# mcu_stm32f427.net
KiCad netlist of a schematic drawn in Altium Designer
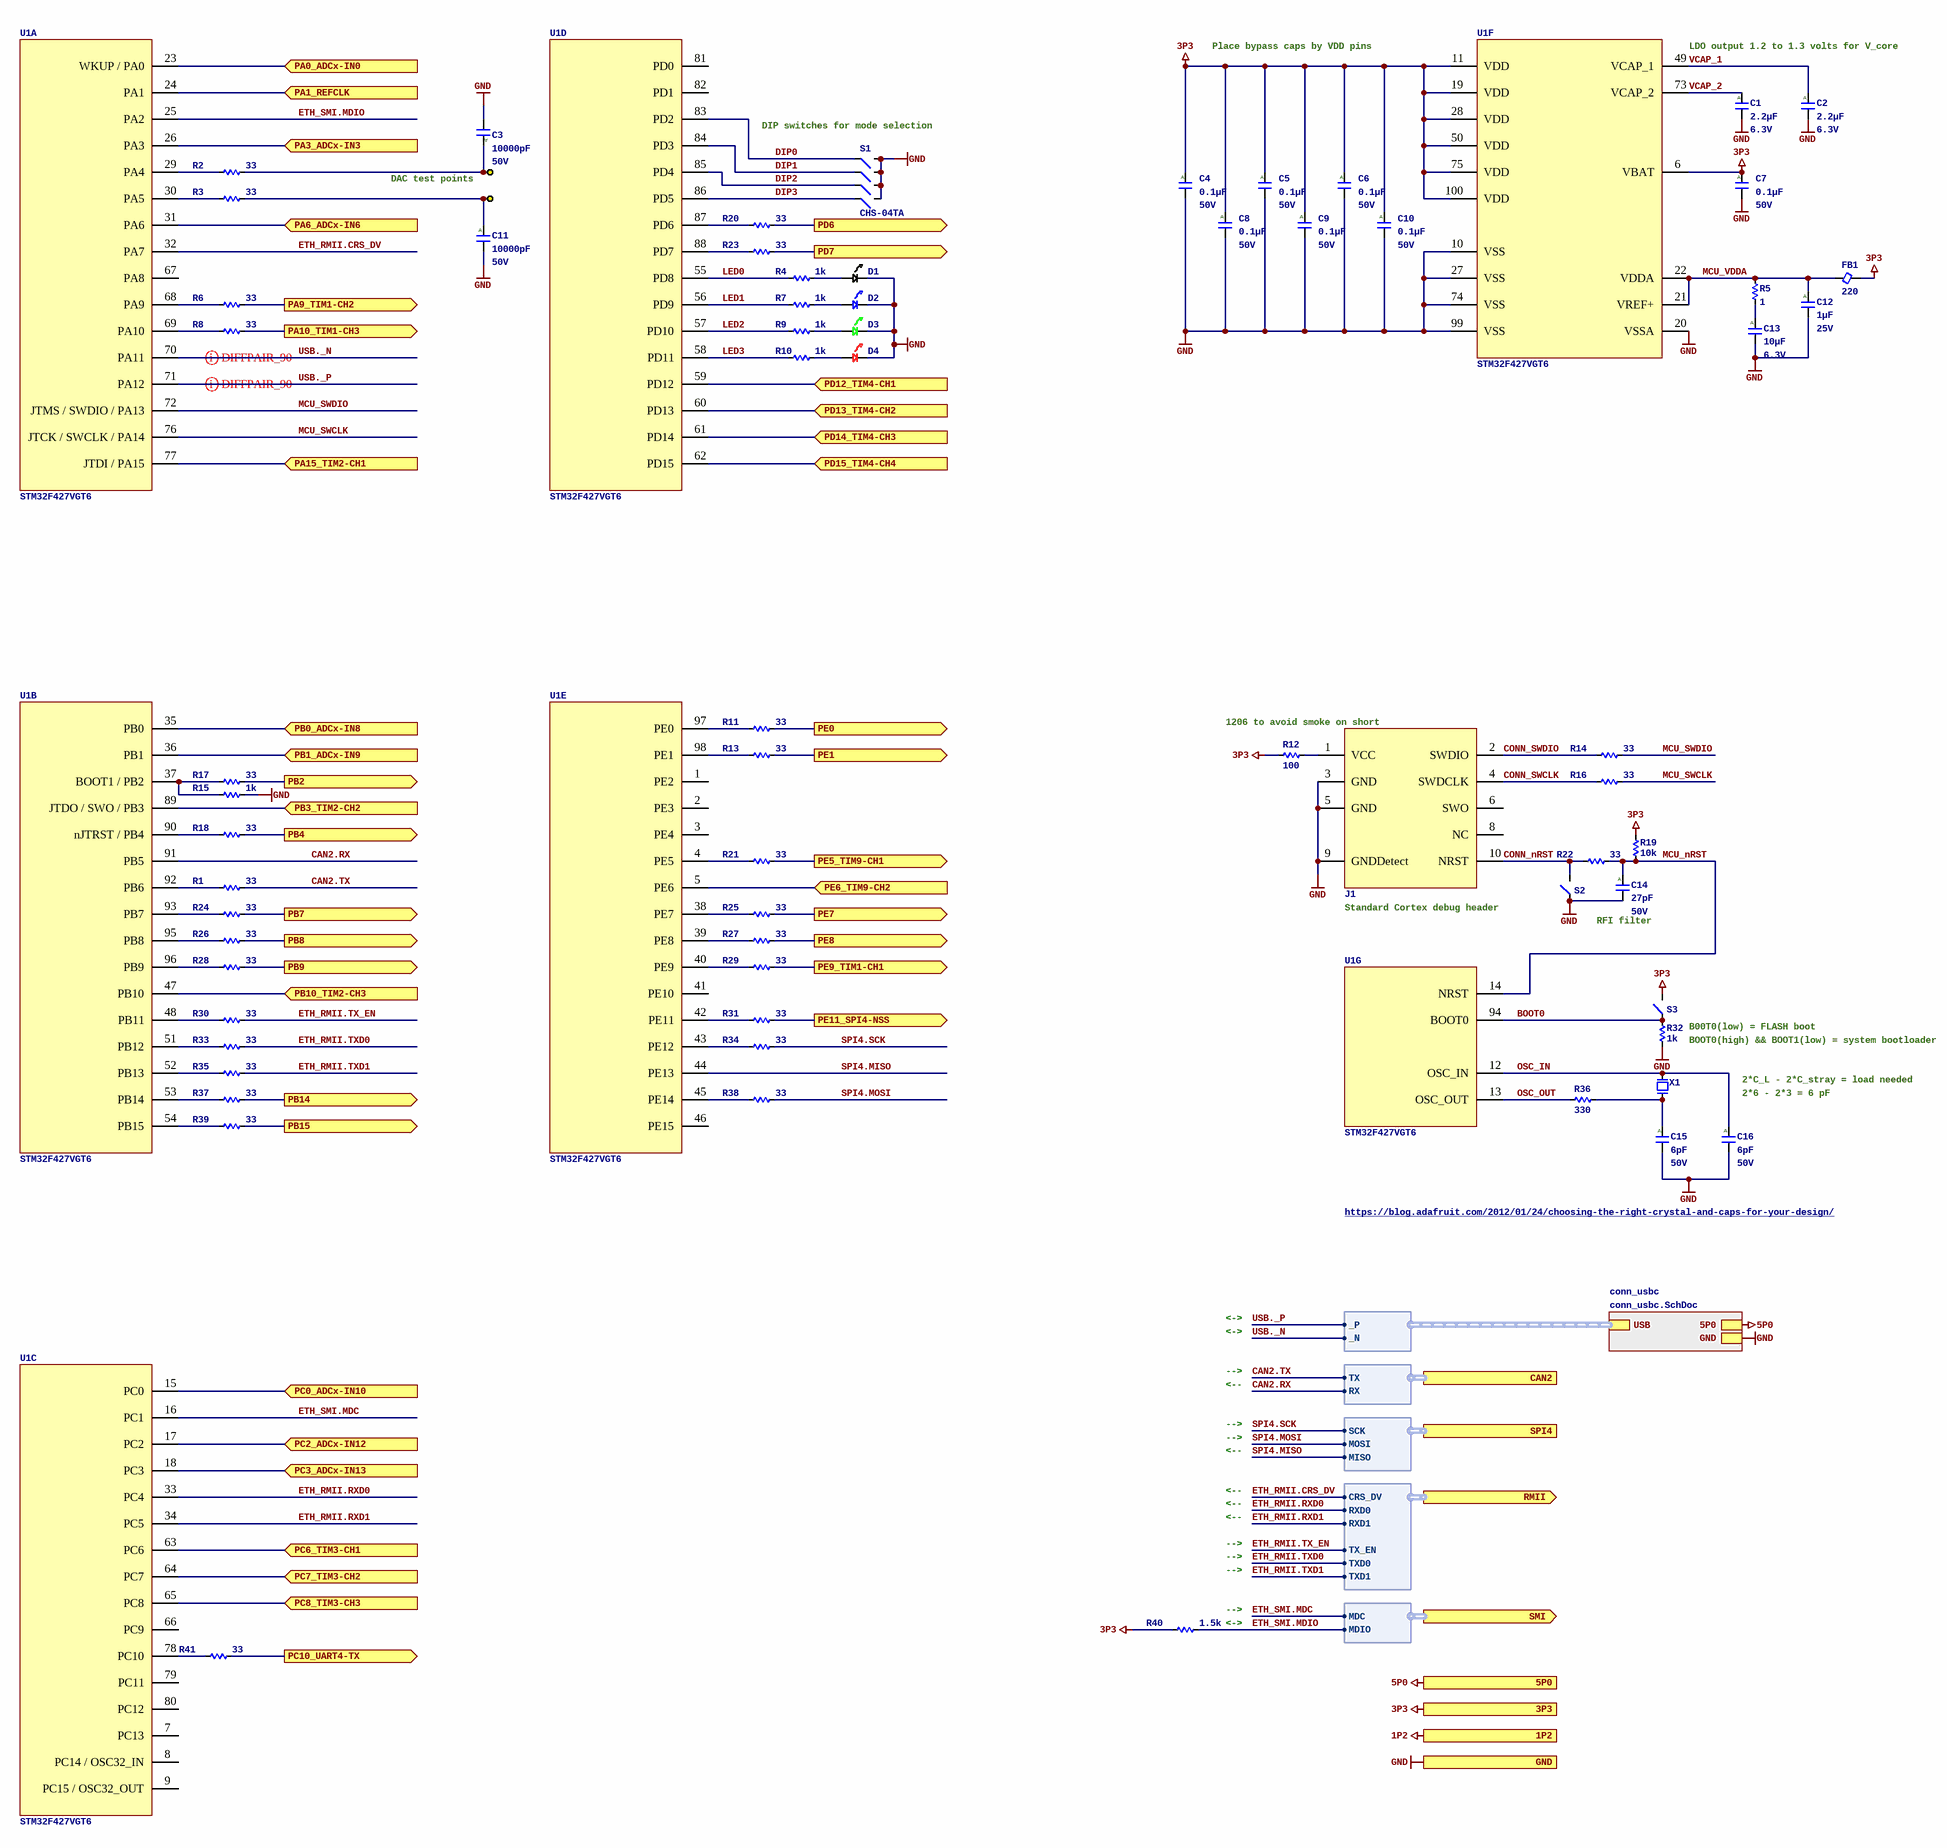
[diagram p0: mcu_stm32f427.SchDoc]

(export (version "E")
  (design (tool "Eeschema 10.0.6"))
  (components
    (comp (ref "C1")
      (value "CGA3E1X7R0J225M080AC")
      (footprint "C0603_0.90MM")
      (description "CAP CER 2.2UF 6.3V X7R 0603")
      (fields
        (field (name "CAPACITANCE") "2.2µF")
        (field (name "VOLTAGE - RATED") "6.3V")
        (field (name "TOLERANCE") "±20%")
        (field (name "MANUFACTURER") "TDK Corporation")
      )
      (libsource (lib "sscp") (part "__template_cap_auto"))
    )
    (comp (ref "C2")
      (value "CGA3E1X7R0J225M080AC")
      (footprint "C0603_0.90MM")
      (description "CAP CER 2.2UF 6.3V X7R 0603")
      (fields
        (field (name "CAPACITANCE") "2.2µF")
        (field (name "VOLTAGE - RATED") "6.3V")
        (field (name "TOLERANCE") "±20%")
        (field (name "MANUFACTURER") "TDK Corporation")
      )
      (libsource (lib "sscp") (part "__template_cap_auto"))
    )
    (comp (ref "C3")
      (value "CGJ2B3X7R1H103K050BB")
      (footprint "C0402_0.50MM")
      (description "CAP CER 10000PF 50V X7R 0402")
      (fields
        (field (name "CAPACITANCE") "10000pF")
        (field (name "VOLTAGE - RATED") "50V")
        (field (name "TOLERANCE") "±10%")
        (field (name "MANUFACTURER") "TDK Corporation")
      )
      (libsource (lib "sscp") (part "__template_cap_auto"))
    )
    (comp (ref "C4")
      (value "CGA2B3X7R1H104M050BB")
      (footprint "C0402_0.55MM")
      (description "CAP CER 0.1UF 50V X7R 0402")
      (fields
        (field (name "CAPACITANCE") "0.1µF")
        (field (name "VOLTAGE - RATED") "50V")
        (field (name "TOLERANCE") "±20%")
        (field (name "MANUFACTURER") "TDK Corporation")
      )
      (libsource (lib "sscp") (part "__template_cap_auto"))
    )
    (comp (ref "C5")
      (value "CGA2B3X7R1H104M050BB")
      (footprint "C0402_0.55MM")
      (description "CAP CER 0.1UF 50V X7R 0402")
      (fields
        (field (name "CAPACITANCE") "0.1µF")
        (field (name "VOLTAGE - RATED") "50V")
        (field (name "TOLERANCE") "±20%")
        (field (name "MANUFACTURER") "TDK Corporation")
      )
      (libsource (lib "sscp") (part "__template_cap_auto"))
    )
    (comp (ref "C6")
      (value "CGA2B3X7R1H104M050BB")
      (footprint "C0402_0.55MM")
      (description "CAP CER 0.1UF 50V X7R 0402")
      (fields
        (field (name "CAPACITANCE") "0.1µF")
        (field (name "VOLTAGE - RATED") "50V")
        (field (name "TOLERANCE") "±20%")
        (field (name "MANUFACTURER") "TDK Corporation")
      )
      (libsource (lib "sscp") (part "__template_cap_auto"))
    )
    (comp (ref "C7")
      (value "CGA2B3X7R1H104M050BB")
      (footprint "C0402_0.55MM")
      (description "CAP CER 0.1UF 50V X7R 0402")
      (fields
        (field (name "CAPACITANCE") "0.1µF")
        (field (name "VOLTAGE - RATED") "50V")
        (field (name "TOLERANCE") "±20%")
        (field (name "MANUFACTURER") "TDK Corporation")
      )
      (libsource (lib "sscp") (part "__template_cap_auto"))
    )
    (comp (ref "C8")
      (value "CGA2B3X7R1H104M050BB")
      (footprint "C0402_0.55MM")
      (description "CAP CER 0.1UF 50V X7R 0402")
      (fields
        (field (name "CAPACITANCE") "0.1µF")
        (field (name "VOLTAGE - RATED") "50V")
        (field (name "TOLERANCE") "±20%")
        (field (name "MANUFACTURER") "TDK Corporation")
      )
      (libsource (lib "sscp") (part "__template_cap_auto"))
    )
    (comp (ref "C9")
      (value "CGA2B3X7R1H104M050BB")
      (footprint "C0402_0.55MM")
      (description "CAP CER 0.1UF 50V X7R 0402")
      (fields
        (field (name "CAPACITANCE") "0.1µF")
        (field (name "VOLTAGE - RATED") "50V")
        (field (name "TOLERANCE") "±20%")
        (field (name "MANUFACTURER") "TDK Corporation")
      )
      (libsource (lib "sscp") (part "__template_cap_auto"))
    )
    (comp (ref "C10")
      (value "CGA2B3X7R1H104M050BB")
      (footprint "C0402_0.55MM")
      (description "CAP CER 0.1UF 50V X7R 0402")
      (fields
        (field (name "CAPACITANCE") "0.1µF")
        (field (name "VOLTAGE - RATED") "50V")
        (field (name "TOLERANCE") "±20%")
        (field (name "MANUFACTURER") "TDK Corporation")
      )
      (libsource (lib "sscp") (part "__template_cap_auto"))
    )
    (comp (ref "C11")
      (value "CGJ2B3X7R1H103K050BB")
      (footprint "C0402_0.50MM")
      (description "CAP CER 10000PF 50V X7R 0402")
      (fields
        (field (name "CAPACITANCE") "10000pF")
        (field (name "VOLTAGE - RATED") "50V")
        (field (name "TOLERANCE") "±10%")
        (field (name "MANUFACTURER") "TDK Corporation")
      )
      (libsource (lib "sscp") (part "__template_cap_auto"))
    )
    (comp (ref "C12")
      (value "CGJ3E1X7R1E105K080AC")
      (footprint "C0603_0.80MM")
      (description "CAP CER 1UF 25V X7R 0603")
      (fields
        (field (name "CAPACITANCE") "1µF")
        (field (name "VOLTAGE - RATED") "25V")
        (field (name "TOLERANCE") "±10%")
        (field (name "MANUFACTURER") "TDK Corporation")
      )
      (libsource (lib "sscp") (part "__template_cap_auto"))
    )
    (comp (ref "C13")
      (value "CGA4J1X7R0J106M125AC")
      (footprint "C0805_1.45MM")
      (description "CAP CER 10UF 6.3V X7R 0805")
      (fields
        (field (name "CAPACITANCE") "10µF")
        (field (name "VOLTAGE - RATED") "6.3V")
        (field (name "TOLERANCE") "±20%")
        (field (name "MANUFACTURER") "TDK Corporation")
      )
      (libsource (lib "sscp") (part "__template_cap_auto"))
    )
    (comp (ref "C14")
      (value "CGA2B2C0G1H270J050BA")
      (footprint "C0402_0.55MM")
      (description "CAP CER 27PF 50V C0G 0402")
      (fields
        (field (name "CAPACITANCE") "27pF")
        (field (name "VOLTAGE - RATED") "50V")
        (field (name "TOLERANCE") "±5%")
        (field (name "MANUFACTURER") "TDK Corporation")
      )
      (libsource (lib "sscp") (part "__template_cap_auto"))
    )
    (comp (ref "C15")
      (value "CGA2B2C0G1H060D050BA")
      (footprint "C0402_0.55MM")
      (description "CAP CER 6PF 50V C0G 0402")
      (fields
        (field (name "CAPACITANCE") "6pF")
        (field (name "VOLTAGE - RATED") "50V")
        (field (name "TOLERANCE") "±0.5pF")
        (field (name "MANUFACTURER") "TDK Corporation")
      )
      (libsource (lib "sscp") (part "__template_cap_auto"))
    )
    (comp (ref "C16")
      (value "CGA2B2C0G1H060D050BA")
      (footprint "C0402_0.55MM")
      (description "CAP CER 6PF 50V C0G 0402")
      (fields
        (field (name "CAPACITANCE") "6pF")
        (field (name "VOLTAGE - RATED") "50V")
        (field (name "TOLERANCE") "±0.5pF")
        (field (name "MANUFACTURER") "TDK Corporation")
      )
      (libsource (lib "sscp") (part "__template_cap_auto"))
    )
    (comp (ref "D1")
      (value "LTW-C193TS5")
      (footprint "LED_0603P_WHITE")
      (description "LED WHITE 0603 SMD")
      (fields (field (name "MANUFACTURER") "Lite-On Inc"))
      (libsource (lib "SSCP") (part "LED_0603_WHITE_LTW-C193TS5"))
    )
    (comp (ref "D2")
      (value "LTST-C191TBKT")
      (footprint "LED_0603P_BLUE")
      (description "LED 468NM BLUE CLEAR 0603 SMD")
      (fields (field (name "MANUFACTURER") "Lite-On Inc"))
      (libsource (lib "SSCP") (part "LED_0603_BLUE_LTST-C191TBKT"))
    )
    (comp (ref "D3")
      (value "LTST-C190GKT")
      (footprint "LED_0603P_GREEN")
      (description "LED GREEN CLEAR 0603 SMD")
      (fields (field (name "MANUFACTURER") "Lite-On Inc"))
      (libsource (lib "SSCP") (part "LED_0603_GREEN_LTST-C190GKT"))
    )
    (comp (ref "D4")
      (value "LTST-C190KRKT")
      (footprint "LED_0603P_RED")
      (description "LED SUPER RED CLEAR 0603 SMD")
      (libsource (lib "SSCP") (part "LED_0603_RED_LTST-C190KRKT"))
    )
    (comp (ref "FB1")
      (value "MPZ1005S221ET000")
      (footprint "FB0402_0.55MM")
      (description "FERRITE BEAD 220 OHM 0402 1LN")
      (fields
        (field (name "IMPEDANCE (OHMS @ 100MHZ)") "220")
        (field (name "MANUFACTURER") "TDK Corporation")
      )
      (libsource (lib "sscp") (part "__template_ferrite"))
    )
    (comp (ref "J1")
      (value "FTSH-105-01-L-DV-K")
      (footprint "FTSH-105-01-L-DV-K_KEYED")
      (description "CONN HEADER 10 POS DUAL .05\" SMD")
      (fields (field (name "MANUFACTURER") "Samtec Inc"))
      (libsource (lib "SSCP") (part "CONN_SWD_CORTEX_DEBUG"))
    )
    (comp (ref "R1")
      (value "ERJ-2RKF33R0X")
      (footprint "R0402_0.40MM")
      (description "RES SMD 33 OHM 1% 1/10W 0402")
      (fields
        (field (name "RESISTANCE") "33")
        (field (name "TOLERANCE") "±1%")
        (field (name "MANUFACTURER") "Panasonic Electronic Components")
      )
      (libsource (lib "sscp") (part "__template_resistor"))
    )
    (comp (ref "R2")
      (value "ERJ-2RKF33R0X")
      (footprint "R0402_0.40MM")
      (description "RES SMD 33 OHM 1% 1/10W 0402")
      (fields
        (field (name "RESISTANCE") "33")
        (field (name "TOLERANCE") "±1%")
        (field (name "MANUFACTURER") "Panasonic Electronic Components")
      )
      (libsource (lib "sscp") (part "__template_resistor"))
    )
    (comp (ref "R3")
      (value "ERJ-2RKF33R0X")
      (footprint "R0402_0.40MM")
      (description "RES SMD 33 OHM 1% 1/10W 0402")
      (fields
        (field (name "RESISTANCE") "33")
        (field (name "TOLERANCE") "±1%")
        (field (name "MANUFACTURER") "Panasonic Electronic Components")
      )
      (libsource (lib "sscp") (part "__template_resistor"))
    )
    (comp (ref "R4")
      (value "~")
      (footprint "R0402_0.40MM")
      (description "RES SMD 1K OHM 1% 1/10W 0402")
      (fields (field (name "RESISTANCE") "1k") (field (name "TOLERANCE") "±1%"))
      (libsource (lib "sscp") (part "__template_resistor"))
    )
    (comp (ref "R5")
      (value "ERJ-2BQF1R0X")
      (footprint "R0402_0.40MM")
      (description "RES SMD 1 OHM 1% 1/6W 0402")
      (fields
        (field (name "RESISTANCE") "1")
        (field (name "TOLERANCE") "±1%")
        (field (name "MANUFACTURER") "Panasonic Electronic Components")
      )
      (libsource (lib "sscp") (part "__template_resistor"))
    )
    (comp (ref "R6")
      (value "ERJ-2RKF33R0X")
      (footprint "R0402_0.40MM")
      (description "RES SMD 33 OHM 1% 1/10W 0402")
      (fields
        (field (name "RESISTANCE") "33")
        (field (name "TOLERANCE") "±1%")
        (field (name "MANUFACTURER") "Panasonic Electronic Components")
      )
      (libsource (lib "sscp") (part "__template_resistor"))
    )
    (comp (ref "R7")
      (value "~")
      (footprint "R0402_0.40MM")
      (description "RES SMD 1K OHM 1% 1/10W 0402")
      (fields (field (name "RESISTANCE") "1k") (field (name "TOLERANCE") "±1%"))
      (libsource (lib "sscp") (part "__template_resistor"))
    )
    (comp (ref "R8")
      (value "ERJ-2RKF33R0X")
      (footprint "R0402_0.40MM")
      (description "RES SMD 33 OHM 1% 1/10W 0402")
      (fields
        (field (name "RESISTANCE") "33")
        (field (name "TOLERANCE") "±1%")
        (field (name "MANUFACTURER") "Panasonic Electronic Components")
      )
      (libsource (lib "sscp") (part "__template_resistor"))
    )
    (comp (ref "R9")
      (value "~")
      (footprint "R0402_0.40MM")
      (description "RES SMD 1K OHM 1% 1/10W 0402")
      (fields (field (name "RESISTANCE") "1k") (field (name "TOLERANCE") "±1%"))
      (libsource (lib "sscp") (part "__template_resistor"))
    )
    (comp (ref "R10")
      (value "~")
      (footprint "R0402_0.40MM")
      (description "RES SMD 1K OHM 1% 1/10W 0402")
      (fields (field (name "RESISTANCE") "1k") (field (name "TOLERANCE") "±1%"))
      (libsource (lib "sscp") (part "__template_resistor"))
    )
    (comp (ref "R11")
      (value "ERJ-2RKF33R0X")
      (footprint "R0402_0.40MM")
      (description "RES SMD 33 OHM 1% 1/10W 0402")
      (fields
        (field (name "RESISTANCE") "33")
        (field (name "TOLERANCE") "±1%")
        (field (name "MANUFACTURER") "Panasonic Electronic Components")
      )
      (libsource (lib "sscp") (part "__template_resistor"))
    )
    (comp (ref "R12")
      (value "ERJ-8ENF1000V")
      (footprint "R1206_0.70MM")
      (description "RES SMD 100 OHM 1% 1/4W 1206")
      (fields
        (field (name "RESISTANCE") "100")
        (field (name "TOLERANCE") "±1%")
        (field (name "MANUFACTURER") "Panasonic Electronic Components")
      )
      (libsource (lib "sscp") (part "__template_resistor"))
    )
    (comp (ref "R13")
      (value "ERJ-2RKF33R0X")
      (footprint "R0402_0.40MM")
      (description "RES SMD 33 OHM 1% 1/10W 0402")
      (fields
        (field (name "RESISTANCE") "33")
        (field (name "TOLERANCE") "±1%")
        (field (name "MANUFACTURER") "Panasonic Electronic Components")
      )
      (libsource (lib "sscp") (part "__template_resistor"))
    )
    (comp (ref "R14")
      (value "ERJ-2RKF33R0X")
      (footprint "R0402_0.40MM")
      (description "RES SMD 33 OHM 1% 1/10W 0402")
      (fields
        (field (name "RESISTANCE") "33")
        (field (name "TOLERANCE") "±1%")
        (field (name "MANUFACTURER") "Panasonic Electronic Components")
      )
      (libsource (lib "sscp") (part "__template_resistor"))
    )
    (comp (ref "R15")
      (value "~")
      (footprint "R0402_0.40MM")
      (description "RES SMD 1K OHM 1% 1/10W 0402")
      (fields (field (name "RESISTANCE") "1k") (field (name "TOLERANCE") "±1%"))
      (libsource (lib "sscp") (part "__template_resistor"))
    )
    (comp (ref "R16")
      (value "ERJ-2RKF33R0X")
      (footprint "R0402_0.40MM")
      (description "RES SMD 33 OHM 1% 1/10W 0402")
      (fields
        (field (name "RESISTANCE") "33")
        (field (name "TOLERANCE") "±1%")
        (field (name "MANUFACTURER") "Panasonic Electronic Components")
      )
      (libsource (lib "sscp") (part "__template_resistor"))
    )
    (comp (ref "R17")
      (value "ERJ-2RKF33R0X")
      (footprint "R0402_0.40MM")
      (description "RES SMD 33 OHM 1% 1/10W 0402")
      (fields
        (field (name "RESISTANCE") "33")
        (field (name "TOLERANCE") "±1%")
        (field (name "MANUFACTURER") "Panasonic Electronic Components")
      )
      (libsource (lib "sscp") (part "__template_resistor"))
    )
    (comp (ref "R18")
      (value "ERJ-2RKF33R0X")
      (footprint "R0402_0.40MM")
      (description "RES SMD 33 OHM 1% 1/10W 0402")
      (fields
        (field (name "RESISTANCE") "33")
        (field (name "TOLERANCE") "±1%")
        (field (name "MANUFACTURER") "Panasonic Electronic Components")
      )
      (libsource (lib "sscp") (part "__template_resistor"))
    )
    (comp (ref "R19")
      (value "~")
      (footprint "R0402_0.40MM")
      (description "RES SMD 10K OHM 1% 1/10W 0402")
      (fields (field (name "RESISTANCE") "10k") (field (name "TOLERANCE") "±1%"))
      (libsource (lib "sscp") (part "__template_resistor"))
    )
    (comp (ref "R20")
      (value "ERJ-2RKF33R0X")
      (footprint "R0402_0.40MM")
      (description "RES SMD 33 OHM 1% 1/10W 0402")
      (fields
        (field (name "RESISTANCE") "33")
        (field (name "TOLERANCE") "±1%")
        (field (name "MANUFACTURER") "Panasonic Electronic Components")
      )
      (libsource (lib "sscp") (part "__template_resistor"))
    )
    (comp (ref "R21")
      (value "ERJ-2RKF33R0X")
      (footprint "R0402_0.40MM")
      (description "RES SMD 33 OHM 1% 1/10W 0402")
      (fields
        (field (name "RESISTANCE") "33")
        (field (name "TOLERANCE") "±1%")
        (field (name "MANUFACTURER") "Panasonic Electronic Components")
      )
      (libsource (lib "sscp") (part "__template_resistor"))
    )
    (comp (ref "R22")
      (value "ERJ-2RKF33R0X")
      (footprint "R0402_0.40MM")
      (description "RES SMD 33 OHM 1% 1/10W 0402")
      (fields
        (field (name "RESISTANCE") "33")
        (field (name "TOLERANCE") "±1%")
        (field (name "MANUFACTURER") "Panasonic Electronic Components")
      )
      (libsource (lib "sscp") (part "__template_resistor"))
    )
    (comp (ref "R23")
      (value "ERJ-2RKF33R0X")
      (footprint "R0402_0.40MM")
      (description "RES SMD 33 OHM 1% 1/10W 0402")
      (fields
        (field (name "RESISTANCE") "33")
        (field (name "TOLERANCE") "±1%")
        (field (name "MANUFACTURER") "Panasonic Electronic Components")
      )
      (libsource (lib "sscp") (part "__template_resistor"))
    )
    (comp (ref "R24")
      (value "ERJ-2RKF33R0X")
      (footprint "R0402_0.40MM")
      (description "RES SMD 33 OHM 1% 1/10W 0402")
      (fields
        (field (name "RESISTANCE") "33")
        (field (name "TOLERANCE") "±1%")
        (field (name "MANUFACTURER") "Panasonic Electronic Components")
      )
      (libsource (lib "sscp") (part "__template_resistor"))
    )
    (comp (ref "R25")
      (value "ERJ-2RKF33R0X")
      (footprint "R0402_0.40MM")
      (description "RES SMD 33 OHM 1% 1/10W 0402")
      (fields
        (field (name "RESISTANCE") "33")
        (field (name "TOLERANCE") "±1%")
        (field (name "MANUFACTURER") "Panasonic Electronic Components")
      )
      (libsource (lib "sscp") (part "__template_resistor"))
    )
    (comp (ref "R26")
      (value "ERJ-2RKF33R0X")
      (footprint "R0402_0.40MM")
      (description "RES SMD 33 OHM 1% 1/10W 0402")
      (fields
        (field (name "RESISTANCE") "33")
        (field (name "TOLERANCE") "±1%")
        (field (name "MANUFACTURER") "Panasonic Electronic Components")
      )
      (libsource (lib "sscp") (part "__template_resistor"))
    )
    (comp (ref "R27")
      (value "ERJ-2RKF33R0X")
      (footprint "R0402_0.40MM")
      (description "RES SMD 33 OHM 1% 1/10W 0402")
      (fields
        (field (name "RESISTANCE") "33")
        (field (name "TOLERANCE") "±1%")
        (field (name "MANUFACTURER") "Panasonic Electronic Components")
      )
      (libsource (lib "sscp") (part "__template_resistor"))
    )
    (comp (ref "R28")
      (value "ERJ-2RKF33R0X")
      (footprint "R0402_0.40MM")
      (description "RES SMD 33 OHM 1% 1/10W 0402")
      (fields
        (field (name "RESISTANCE") "33")
        (field (name "TOLERANCE") "±1%")
        (field (name "MANUFACTURER") "Panasonic Electronic Components")
      )
      (libsource (lib "sscp") (part "__template_resistor"))
    )
    (comp (ref "R29")
      (value "ERJ-2RKF33R0X")
      (footprint "R0402_0.40MM")
      (description "RES SMD 33 OHM 1% 1/10W 0402")
      (fields
        (field (name "RESISTANCE") "33")
        (field (name "TOLERANCE") "±1%")
        (field (name "MANUFACTURER") "Panasonic Electronic Components")
      )
      (libsource (lib "sscp") (part "__template_resistor"))
    )
    (comp (ref "R30")
      (value "ERJ-2RKF33R0X")
      (footprint "R0402_0.40MM")
      (description "RES SMD 33 OHM 1% 1/10W 0402")
      (fields
        (field (name "RESISTANCE") "33")
        (field (name "TOLERANCE") "±1%")
        (field (name "MANUFACTURER") "Panasonic Electronic Components")
      )
      (libsource (lib "sscp") (part "__template_resistor"))
    )
    (comp (ref "R31")
      (value "ERJ-2RKF33R0X")
      (footprint "R0402_0.40MM")
      (description "RES SMD 33 OHM 1% 1/10W 0402")
      (fields
        (field (name "RESISTANCE") "33")
        (field (name "TOLERANCE") "±1%")
        (field (name "MANUFACTURER") "Panasonic Electronic Components")
      )
      (libsource (lib "sscp") (part "__template_resistor"))
    )
    (comp (ref "R32")
      (value "~")
      (footprint "R0402_0.40MM")
      (description "RES SMD 1K OHM 1% 1/10W 0402")
      (fields (field (name "RESISTANCE") "1k") (field (name "TOLERANCE") "±1%"))
      (libsource (lib "sscp") (part "__template_resistor"))
    )
    (comp (ref "R33")
      (value "ERJ-2RKF33R0X")
      (footprint "R0402_0.40MM")
      (description "RES SMD 33 OHM 1% 1/10W 0402")
      (fields
        (field (name "RESISTANCE") "33")
        (field (name "TOLERANCE") "±1%")
        (field (name "MANUFACTURER") "Panasonic Electronic Components")
      )
      (libsource (lib "sscp") (part "__template_resistor"))
    )
    (comp (ref "R34")
      (value "ERJ-2RKF33R0X")
      (footprint "R0402_0.40MM")
      (description "RES SMD 33 OHM 1% 1/10W 0402")
      (fields
        (field (name "RESISTANCE") "33")
        (field (name "TOLERANCE") "±1%")
        (field (name "MANUFACTURER") "Panasonic Electronic Components")
      )
      (libsource (lib "sscp") (part "__template_resistor"))
    )
    (comp (ref "R35")
      (value "ERJ-2RKF33R0X")
      (footprint "R0402_0.40MM")
      (description "RES SMD 33 OHM 1% 1/10W 0402")
      (fields
        (field (name "RESISTANCE") "33")
        (field (name "TOLERANCE") "±1%")
        (field (name "MANUFACTURER") "Panasonic Electronic Components")
      )
      (libsource (lib "sscp") (part "__template_resistor"))
    )
    (comp (ref "R36")
      (value "ERJ-PA2F3300X")
      (footprint "R0402_0.40MM")
      (description "RES SMD 330 OHM 1% 1/5W 0402")
      (fields
        (field (name "RESISTANCE") "330")
        (field (name "TOLERANCE") "±1%")
        (field (name "MANUFACTURER") "Panasonic Electronic Components")
      )
      (libsource (lib "sscp") (part "__template_resistor"))
    )
    (comp (ref "R37")
      (value "ERJ-2RKF33R0X")
      (footprint "R0402_0.40MM")
      (description "RES SMD 33 OHM 1% 1/10W 0402")
      (fields
        (field (name "RESISTANCE") "33")
        (field (name "TOLERANCE") "±1%")
        (field (name "MANUFACTURER") "Panasonic Electronic Components")
      )
      (libsource (lib "sscp") (part "__template_resistor"))
    )
    (comp (ref "R38")
      (value "ERJ-2RKF33R0X")
      (footprint "R0402_0.40MM")
      (description "RES SMD 33 OHM 1% 1/10W 0402")
      (fields
        (field (name "RESISTANCE") "33")
        (field (name "TOLERANCE") "±1%")
        (field (name "MANUFACTURER") "Panasonic Electronic Components")
      )
      (libsource (lib "sscp") (part "__template_resistor"))
    )
    (comp (ref "R39")
      (value "ERJ-2RKF33R0X")
      (footprint "R0402_0.40MM")
      (description "RES SMD 33 OHM 1% 1/10W 0402")
      (fields
        (field (name "RESISTANCE") "33")
        (field (name "TOLERANCE") "±1%")
        (field (name "MANUFACTURER") "Panasonic Electronic Components")
      )
      (libsource (lib "sscp") (part "__template_resistor"))
    )
    (comp (ref "R40")
      (value "ERJ-2RKF1501X")
      (footprint "R0402_0.40MM")
      (description "RES SMD 1.5K OHM 1% 1/10W 0402")
      (fields
        (field (name "RESISTANCE") "1.5k")
        (field (name "TOLERANCE") "±1%")
        (field (name "MANUFACTURER") "Panasonic Electronic Components")
      )
      (libsource (lib "sscp") (part "__template_resistor"))
    )
    (comp (ref "R41")
      (value "ERJ-2RKF33R0X")
      (footprint "R0402_0.40MM")
      (description "RES SMD 33 OHM 1% 1/10W 0402")
      (fields
        (field (name "RESISTANCE") "33")
        (field (name "TOLERANCE") "±1%")
        (field (name "MANUFACTURER") "Panasonic Electronic Components")
      )
      (libsource (lib "sscp") (part "__template_resistor"))
    )
    (comp (ref "S1")
      (value "CHS-04TA")
      (footprint "SWITCH_NIDEC_CHS-04TA")
      (description "DIP Switch, Slide, SPST, Flush, Recessed, 6VDC, 100mA, CHS Series ¦ Nidec Components CHS-04TA")
      (fields (field (name "MANUFACTURER") "Nidec Copal"))
      (libsource (lib "SSCP") (part "SWITCH_CHS-04TA"))
    )
    (comp (ref "S2")
      (value "TS-1092S-B3D2-G")
      (footprint "SWITCH_TS-1092S-B3D2-G")
      (description "SWITCH TACTILE SPST-NO")
      (fields (field (name "MANUFACTURER") "Yuandi"))
      (libsource (lib "SSCP") (part "SWITCH_TS-1092S-B3D2-G"))
    )
    (comp (ref "S3")
      (value "TS-1092S-B3D2-G")
      (footprint "SWITCH_TS-1092S-B3D2-G")
      (description "SWITCH TACTILE SPST-NO")
      (fields (field (name "MANUFACTURER") "Yuandi"))
      (libsource (lib "SSCP") (part "SWITCH_TS-1092S-B3D2-G"))
    )
    (comp (ref "TP1")
      (value "RH-5002")
      (footprint "TP_RH-5002")
      (description "THT white clip turret")
      (fields (field (name "MANUFACTURER") "ronghe"))
      (libsource (lib "sscp") (part "__template_testpoint"))
    )
    (comp (ref "TP2")
      (value "RH-5002")
      (footprint "TP_RH-5002")
      (description "THT white clip turret")
      (fields (field (name "MANUFACTURER") "ronghe"))
      (libsource (lib "sscp") (part "__template_testpoint"))
    )
    (comp (ref "U1")
      (value "STM32F427VGT6")
      (footprint "100TQFP14")
      (description "ARM Cortex®-M4 STM32F4 Microcontroller IC 32-Bit 180MHz 1MB (1M x 8) FLASH 100-LQFP (14x14)")
      (fields
        (field (name "MANUFACTURER PART NUMBER") "STM32F427VGT6")
        (field (name "MANUFACTURER") "ST Microelectronics")
      )
      (libsource (lib "SSCP") (part "MCU_STM32F427VGT6"))
    )
    (comp (ref "X1")
      (value "XTAL_XRCGB25M000F3A00R0")
      (footprint "4_SMD_2.0X1.6MM")
      (description "CRYSTAL 25.000MHZ 6PF SMD")
      (fields
        (field (name "MANUFACTURER") "Murata")
        (field (name "MANUFACTURER PART NUMBER") "XRCGB25M000F3A00R0")
      )
      (libsource (lib "SSCP") (part "XTAL_XRCGB25M000F3A00R0"))
    )
  )
  (nets
    (net (code "6") (name "/BOOT0") (class "Default")
      (node (ref "R32") (pin "1") (pintype "passive"))
      (node (ref "S3") (pin "1") (pintype "passive"))
      (node (ref "U1") (pin "94") (pinfunction "BOOT0_94") (pintype "passive"))
    )
    (net (code "7") (name "/CAN2.RX") (class "Default")
      (node (ref "U1") (pin "91") (pinfunction "PB5_91") (pintype "passive"))
    )
    (net (code "8") (name "/CAN2.TX") (class "Default") (node (ref "R1") (pin "1") (pintype "passive")))
    (net (code "9") (name "/CONN_SWCLK") (class "Default")
      (node (ref "J1") (pin "4") (pinfunction "SWDCLK_4") (pintype "passive"))
      (node (ref "R16") (pin "2") (pintype "passive"))
    )
    (net (code "10") (name "/CONN_SWDIO") (class "Default")
      (node (ref "J1") (pin "2") (pinfunction "SWDIO_2") (pintype "passive"))
      (node (ref "R14") (pin "2") (pintype "passive"))
    )
    (net (code "11") (name "/CONN_nRST") (class "Default")
      (node (ref "J1") (pin "10") (pinfunction "NRST_10") (pintype "passive"))
      (node (ref "R22") (pin "2") (pintype "passive"))
      (node (ref "S2") (pin "2") (pintype "passive"))
    )
    (net (code "12") (name "/DIP0") (class "Default")
      (node (ref "S1") (pin "7") (pintype "passive"))
      (node (ref "U1") (pin "83") (pinfunction "PD2_83") (pintype "passive"))
    )
    (net (code "13") (name "/DIP1") (class "Default")
      (node (ref "S1") (pin "5") (pintype "passive"))
      (node (ref "U1") (pin "84") (pinfunction "PD3_84") (pintype "passive"))
    )
    (net (code "14") (name "/DIP2") (class "Default")
      (node (ref "S1") (pin "3") (pintype "passive"))
      (node (ref "U1") (pin "85") (pinfunction "PD4_85") (pintype "passive"))
    )
    (net (code "15") (name "/DIP3") (class "Default")
      (node (ref "S1") (pin "1") (pintype "passive"))
      (node (ref "U1") (pin "86") (pinfunction "PD5_86") (pintype "passive"))
    )
    (net (code "16") (name "/ETH_RMII.CRS_DV") (class "Default")
      (node (ref "U1") (pin "32") (pinfunction "PA7_32") (pintype "passive"))
    )
    (net (code "17") (name "/ETH_RMII.RXD0") (class "Default")
      (node (ref "U1") (pin "33") (pinfunction "PC4_33") (pintype "passive"))
    )
    (net (code "18") (name "/ETH_RMII.RXD1") (class "Default")
      (node (ref "U1") (pin "34") (pinfunction "PC5_34") (pintype "passive"))
    )
    (net (code "19") (name "/ETH_RMII.TXD0") (class "Default")
      (node (ref "R33") (pin "1") (pintype "passive"))
    )
    (net (code "20") (name "/ETH_RMII.TXD1") (class "Default")
      (node (ref "R35") (pin "1") (pintype "passive"))
    )
    (net (code "21") (name "/ETH_RMII.TX_EN") (class "Default")
      (node (ref "R30") (pin "1") (pintype "passive"))
    )
    (net (code "22") (name "/ETH_SMI.MDC") (class "Default")
      (node (ref "U1") (pin "16") (pinfunction "PC1_16") (pintype "passive"))
    )
    (net (code "23") (name "/ETH_SMI.MDIO") (class "Default")
      (node (ref "R40") (pin "1") (pintype "passive"))
      (node (ref "U1") (pin "25") (pinfunction "PA2_25") (pintype "passive"))
    )
    (net (code "24") (name "/LED0") (class "Default")
      (node (ref "R4") (pin "2") (pintype "passive"))
      (node (ref "U1") (pin "55") (pinfunction "PD8_55") (pintype "passive"))
    )
    (net (code "25") (name "/LED1") (class "Default")
      (node (ref "R7") (pin "2") (pintype "passive"))
      (node (ref "U1") (pin "56") (pinfunction "PD9_56") (pintype "passive"))
    )
    (net (code "26") (name "/LED2") (class "Default")
      (node (ref "R9") (pin "2") (pintype "passive"))
      (node (ref "U1") (pin "57") (pinfunction "PD10_57") (pintype "passive"))
    )
    (net (code "27") (name "/LED3") (class "Default")
      (node (ref "R10") (pin "2") (pintype "passive"))
      (node (ref "U1") (pin "58") (pinfunction "PD11_58") (pintype "passive"))
    )
    (net (code "28") (name "/MCU_SWCLK") (class "Default")
      (node (ref "R16") (pin "1") (pintype "passive"))
      (node (ref "U1") (pin "76") (pinfunction "JTCK_/_SWCLK_/_PA14_76") (pintype "passive"))
    )
    (net (code "29") (name "/MCU_SWDIO") (class "Default")
      (node (ref "R14") (pin "1") (pintype "passive"))
      (node (ref "U1") (pin "72") (pinfunction "JTMS_/_SWDIO_/_PA13_72") (pintype "passive"))
    )
    (net (code "30") (name "/MCU_VDDA") (class "Default")
      (node (ref "C12") (pin "1") (pintype "passive"))
      (node (ref "FB1") (pin "1") (pintype "passive"))
      (node (ref "R5") (pin "2") (pintype "passive"))
      (node (ref "U1") (pin "21") (pinfunction "VREF+_21") (pintype "passive"))
      (node (ref "U1") (pin "22") (pinfunction "VDDA_22") (pintype "passive"))
    )
    (net (code "31") (name "/MCU_nRST") (class "Default")
      (node (ref "C14") (pin "1") (pintype "passive"))
      (node (ref "R19") (pin "2") (pintype "passive"))
      (node (ref "R22") (pin "1") (pintype "passive"))
      (node (ref "U1") (pin "14") (pinfunction "NRST_14") (pintype "passive"))
    )
    (net (code "32") (name "/OSC_IN") (class "Default")
      (node (ref "C16") (pin "1") (pintype "passive"))
      (node (ref "U1") (pin "12") (pinfunction "OSC_IN_12") (pintype "passive"))
      (node (ref "X1") (pin "3") (pinfunction "3_3") (pintype "passive"))
    )
    (net (code "33") (name "/OSC_OUT") (class "Default")
      (node (ref "R36") (pin "1") (pintype "passive"))
      (node (ref "U1") (pin "13") (pinfunction "OSC_OUT_13") (pintype "passive"))
    )
    (net (code "34") (name "/PA0_ADCx-IN0") (class "Default")
      (node (ref "U1") (pin "23") (pinfunction "WKUP_/_PA0_23") (pintype "passive"))
    )
    (net (code "35") (name "/PA1_REFCLK") (class "Default")
      (node (ref "U1") (pin "24") (pinfunction "PA1_24") (pintype "passive"))
    )
    (net (code "36") (name "/PA3_ADCx-IN3") (class "Default")
      (node (ref "U1") (pin "26") (pinfunction "PA3_26") (pintype "passive"))
    )
    (net (code "37") (name "/PA6_ADCx-IN6") (class "Default")
      (node (ref "U1") (pin "31") (pinfunction "PA6_31") (pintype "passive"))
    )
    (net (code "38") (name "/PA9_TIM1-CH2") (class "Default") (node (ref "R6") (pin "1") (pintype "passive")))
    (net (code "39") (name "/PA10_TIM1-CH3") (class "Default")
      (node (ref "R8") (pin "1") (pintype "passive"))
    )
    (net (code "40") (name "/PA15_TIM2-CH1") (class "Default")
      (node (ref "U1") (pin "77") (pinfunction "JTDI_/_PA15_77") (pintype "passive"))
    )
    (net (code "41") (name "/PB0_ADCx-IN8") (class "Default")
      (node (ref "U1") (pin "35") (pinfunction "PB0_35") (pintype "passive"))
    )
    (net (code "42") (name "/PB1_ADCx-IN9") (class "Default")
      (node (ref "U1") (pin "36") (pinfunction "PB1_36") (pintype "passive"))
    )
    (net (code "43") (name "/PB2") (class "Default") (node (ref "R17") (pin "1") (pintype "passive")))
    (net (code "44") (name "/PB3_TIM2-CH2") (class "Default")
      (node (ref "U1") (pin "89") (pinfunction "JTDO_/_SWO_/_PB3_89") (pintype "passive"))
    )
    (net (code "45") (name "/PB4") (class "Default") (node (ref "R18") (pin "1") (pintype "passive")))
    (net (code "46") (name "/PB7") (class "Default") (node (ref "R24") (pin "1") (pintype "passive")))
    (net (code "47") (name "/PB8") (class "Default") (node (ref "R26") (pin "1") (pintype "passive")))
    (net (code "48") (name "/PB9") (class "Default") (node (ref "R28") (pin "1") (pintype "passive")))
    (net (code "49") (name "/PB10_TIM2-CH3") (class "Default")
      (node (ref "U1") (pin "47") (pinfunction "PB10_47") (pintype "passive"))
    )
    (net (code "50") (name "/PB14") (class "Default") (node (ref "R37") (pin "1") (pintype "passive")))
    (net (code "51") (name "/PB15") (class "Default") (node (ref "R39") (pin "1") (pintype "passive")))
    (net (code "52") (name "/PC0_ADCx-IN10") (class "Default")
      (node (ref "U1") (pin "15") (pinfunction "PC0_15") (pintype "passive"))
    )
    (net (code "53") (name "/PC2_ADCx-IN12") (class "Default")
      (node (ref "U1") (pin "17") (pinfunction "PC2_17") (pintype "passive"))
    )
    (net (code "54") (name "/PC3_ADCx-IN13") (class "Default")
      (node (ref "U1") (pin "18") (pinfunction "PC3_18") (pintype "passive"))
    )
    (net (code "55") (name "/PC6_TIM3-CH1") (class "Default")
      (node (ref "U1") (pin "63") (pinfunction "PC6_63") (pintype "passive"))
    )
    (net (code "56") (name "/PC7_TIM3-CH2") (class "Default")
      (node (ref "U1") (pin "64") (pinfunction "PC7_64") (pintype "passive"))
    )
    (net (code "57") (name "/PC8_TIM3-CH3") (class "Default")
      (node (ref "U1") (pin "65") (pinfunction "PC8_65") (pintype "passive"))
    )
    (net (code "58") (name "/PC10_UART4-TX") (class "Default")
      (node (ref "R41") (pin "1") (pintype "passive"))
    )
    (net (code "59") (name "/PD6") (class "Default") (node (ref "R20") (pin "1") (pintype "passive")))
    (net (code "60") (name "/PD7") (class "Default") (node (ref "R23") (pin "1") (pintype "passive")))
    (net (code "61") (name "/PD12_TIM4-CH1") (class "Default")
      (node (ref "U1") (pin "59") (pinfunction "PD12_59") (pintype "passive"))
    )
    (net (code "62") (name "/PD13_TIM4-CH2") (class "Default")
      (node (ref "U1") (pin "60") (pinfunction "PD13_60") (pintype "passive"))
    )
    (net (code "63") (name "/PD14_TIM4-CH3") (class "Default")
      (node (ref "U1") (pin "61") (pinfunction "PD14_61") (pintype "passive"))
    )
    (net (code "64") (name "/PD15_TIM4-CH4") (class "Default")
      (node (ref "U1") (pin "62") (pinfunction "PD15_62") (pintype "passive"))
    )
    (net (code "65") (name "/PE0") (class "Default") (node (ref "R11") (pin "1") (pintype "passive")))
    (net (code "66") (name "/PE1") (class "Default") (node (ref "R13") (pin "1") (pintype "passive")))
    (net (code "67") (name "/PE5_TIM9-CH1") (class "Default")
      (node (ref "R21") (pin "1") (pintype "passive"))
    )
    (net (code "68") (name "/PE6_TIM9-CH2") (class "Default")
      (node (ref "U1") (pin "5") (pinfunction "PE6_5") (pintype "passive"))
    )
    (net (code "69") (name "/PE7") (class "Default") (node (ref "R25") (pin "1") (pintype "passive")))
    (net (code "70") (name "/PE8") (class "Default") (node (ref "R27") (pin "1") (pintype "passive")))
    (net (code "71") (name "/PE9_TIM1-CH1") (class "Default")
      (node (ref "R29") (pin "1") (pintype "passive"))
    )
    (net (code "72") (name "/PE11_SPI4-NSS") (class "Default")
      (node (ref "R31") (pin "1") (pintype "passive"))
    )
    (net (code "73") (name "/SPI4.MISO") (class "Default")
      (node (ref "U1") (pin "44") (pinfunction "PE13_44") (pintype "passive"))
    )
    (net (code "74") (name "/SPI4.MOSI") (class "Default") (node (ref "R38") (pin "1") (pintype "passive")))
    (net (code "75") (name "/SPI4.SCK") (class "Default") (node (ref "R34") (pin "1") (pintype "passive")))
    (net (code "76") (name "/USB._N") (class "Default")
      (node (ref "U1") (pin "70") (pinfunction "PA11_70") (pintype "passive"))
    )
    (net (code "77") (name "/USB._P") (class "Default")
      (node (ref "U1") (pin "71") (pinfunction "PA12_71") (pintype "passive"))
    )
    (net (code "78") (name "/VCAP_1") (class "Default")
      (node (ref "C2") (pin "1") (pintype "passive"))
      (node (ref "U1") (pin "49") (pinfunction "VCAP_1_49") (pintype "passive"))
    )
    (net (code "79") (name "/VCAP_2") (class "Default")
      (node (ref "C1") (pin "1") (pintype "passive"))
      (node (ref "U1") (pin "73") (pinfunction "VCAP_2_73") (pintype "passive"))
    )
    (net (code "86") (name "3P3") (class "Default")
      (node (ref "C10") (pin "1") (pintype "passive"))
      (node (ref "C4") (pin "1") (pintype "passive"))
      (node (ref "C5") (pin "1") (pintype "passive"))
      (node (ref "C6") (pin "1") (pintype "passive"))
      (node (ref "C7") (pin "1") (pintype "passive"))
      (node (ref "C8") (pin "1") (pintype "passive"))
      (node (ref "C9") (pin "1") (pintype "passive"))
      (node (ref "FB1") (pin "2") (pintype "passive"))
      (node (ref "R12") (pin "2") (pintype "passive"))
      (node (ref "R19") (pin "1") (pintype "passive"))
      (node (ref "R40") (pin "2") (pintype "passive"))
      (node (ref "S3") (pin "2") (pintype "passive"))
      (node (ref "U1") (pin "100") (pinfunction "VDD_100") (pintype "passive"))
      (node (ref "U1") (pin "11") (pinfunction "VDD_11") (pintype "passive"))
      (node (ref "U1") (pin "19") (pinfunction "VDD_19") (pintype "passive"))
      (node (ref "U1") (pin "28") (pinfunction "VDD_28") (pintype "passive"))
      (node (ref "U1") (pin "50") (pinfunction "VDD_50") (pintype "passive"))
      (node (ref "U1") (pin "6") (pinfunction "VBAT_6") (pintype "passive"))
      (node (ref "U1") (pin "75") (pinfunction "VDD_75") (pintype "passive"))
    )
    (net (code "88") (name "GND") (class "Default")
      (node (ref "C1") (pin "2") (pintype "passive"))
      (node (ref "C10") (pin "2") (pintype "passive"))
      (node (ref "C11") (pin "2") (pintype "passive"))
      (node (ref "C12") (pin "2") (pintype "passive"))
      (node (ref "C13") (pin "2") (pintype "passive"))
      (node (ref "C14") (pin "2") (pintype "passive"))
      (node (ref "C15") (pin "2") (pintype "passive"))
      (node (ref "C16") (pin "2") (pintype "passive"))
      (node (ref "C2") (pin "2") (pintype "passive"))
      (node (ref "C3") (pin "2") (pintype "passive"))
      (node (ref "C4") (pin "2") (pintype "passive"))
      (node (ref "C5") (pin "2") (pintype "passive"))
      (node (ref "C6") (pin "2") (pintype "passive"))
      (node (ref "C7") (pin "2") (pintype "passive"))
      (node (ref "C8") (pin "2") (pintype "passive"))
      (node (ref "C9") (pin "2") (pintype "passive"))
      (node (ref "D1") (pin "1") (pintype "passive"))
      (node (ref "D2") (pin "1") (pintype "passive"))
      (node (ref "D3") (pin "1") (pintype "passive"))
      (node (ref "D4") (pin "1") (pintype "passive"))
      (node (ref "J1") (pin "3") (pinfunction "GND_3") (pintype "passive"))
      (node (ref "J1") (pin "5") (pinfunction "GND_5") (pintype "passive"))
      (node (ref "J1") (pin "9") (pinfunction "GNDDetect_9") (pintype "passive"))
      (node (ref "R15") (pin "1") (pintype "passive"))
      (node (ref "R32") (pin "2") (pintype "passive"))
      (node (ref "S1") (pin "2") (pintype "passive"))
      (node (ref "S1") (pin "4") (pintype "passive"))
      (node (ref "S1") (pin "6") (pintype "passive"))
      (node (ref "S1") (pin "8") (pintype "passive"))
      (node (ref "S2") (pin "1") (pintype "passive"))
      (node (ref "U1") (pin "10") (pinfunction "VSS_10") (pintype "passive"))
      (node (ref "U1") (pin "20") (pinfunction "VSSA_20") (pintype "passive"))
      (node (ref "U1") (pin "27") (pinfunction "VSS_27") (pintype "passive"))
      (node (ref "U1") (pin "74") (pinfunction "VSS_74") (pintype "passive"))
      (node (ref "U1") (pin "99") (pinfunction "VSS_99") (pintype "passive"))
    )
    (net (code "89") (name "Net-(C3-Pad1)") (class "Default")
      (node (ref "C3") (pin "1") (pintype "passive"))
      (node (ref "R2") (pin "1") (pintype "passive"))
      (node (ref "TP1") (pin "1") (pintype "passive"))
    )
    (net (code "90") (name "Net-(C11-Pad1)") (class "Default")
      (node (ref "C11") (pin "1") (pintype "passive"))
      (node (ref "R3") (pin "1") (pintype "passive"))
      (node (ref "TP2") (pin "1") (pintype "passive"))
    )
    (net (code "91") (name "Net-(C13-Pad1)") (class "Default")
      (node (ref "C13") (pin "1") (pintype "passive"))
      (node (ref "R5") (pin "1") (pintype "passive"))
    )
    (net (code "92") (name "Net-(C15-Pad1)") (class "Default")
      (node (ref "C15") (pin "1") (pintype "passive"))
      (node (ref "R36") (pin "2") (pintype "passive"))
      (node (ref "X1") (pin "1") (pinfunction "1_1") (pintype "passive"))
    )
    (net (code "93") (name "Net-(D1-Pad2)") (class "Default")
      (node (ref "D1") (pin "2") (pintype "passive"))
      (node (ref "R4") (pin "1") (pintype "passive"))
    )
    (net (code "94") (name "Net-(D2-Pad2)") (class "Default")
      (node (ref "D2") (pin "2") (pintype "passive"))
      (node (ref "R7") (pin "1") (pintype "passive"))
    )
    (net (code "95") (name "Net-(D3-Pad2)") (class "Default")
      (node (ref "D3") (pin "2") (pintype "passive"))
      (node (ref "R9") (pin "1") (pintype "passive"))
    )
    (net (code "96") (name "Net-(D4-Pad2)") (class "Default")
      (node (ref "D4") (pin "2") (pintype "passive"))
      (node (ref "R10") (pin "1") (pintype "passive"))
    )
    (net (code "97") (name "Net-(J1-VCC)") (class "Default")
      (node (ref "J1") (pin "1") (pinfunction "VCC_1") (pintype "passive"))
      (node (ref "R12") (pin "1") (pintype "passive"))
    )
    (net (code "98") (name "Net-(U1A-PA4)") (class "Default")
      (node (ref "R2") (pin "2") (pintype "passive"))
      (node (ref "U1") (pin "29") (pinfunction "PA4_29") (pintype "passive"))
    )
    (net (code "99") (name "Net-(U1A-PA5)") (class "Default")
      (node (ref "R3") (pin "2") (pintype "passive"))
      (node (ref "U1") (pin "30") (pinfunction "PA5_30") (pintype "passive"))
    )
    (net (code "100") (name "Net-(U1A-PA9)") (class "Default")
      (node (ref "R6") (pin "2") (pintype "passive"))
      (node (ref "U1") (pin "68") (pinfunction "PA9_68") (pintype "passive"))
    )
    (net (code "101") (name "Net-(U1A-PA10)") (class "Default")
      (node (ref "R8") (pin "2") (pintype "passive"))
      (node (ref "U1") (pin "69") (pinfunction "PA10_69") (pintype "passive"))
    )
    (net (code "102") (name "Net-(U1B-BOOT1_{slash}_PB2)") (class "Default")
      (node (ref "R15") (pin "2") (pintype "passive"))
      (node (ref "R17") (pin "2") (pintype "passive"))
      (node (ref "U1") (pin "37") (pinfunction "BOOT1_/_PB2_37") (pintype "passive"))
    )
    (net (code "103") (name "Net-(U1B-PB6)") (class "Default")
      (node (ref "R1") (pin "2") (pintype "passive"))
      (node (ref "U1") (pin "92") (pinfunction "PB6_92") (pintype "passive"))
    )
    (net (code "104") (name "Net-(U1B-PB7)") (class "Default")
      (node (ref "R24") (pin "2") (pintype "passive"))
      (node (ref "U1") (pin "93") (pinfunction "PB7_93") (pintype "passive"))
    )
    (net (code "105") (name "Net-(U1B-PB8)") (class "Default")
      (node (ref "R26") (pin "2") (pintype "passive"))
      (node (ref "U1") (pin "95") (pinfunction "PB8_95") (pintype "passive"))
    )
    (net (code "106") (name "Net-(U1B-PB9)") (class "Default")
      (node (ref "R28") (pin "2") (pintype "passive"))
      (node (ref "U1") (pin "96") (pinfunction "PB9_96") (pintype "passive"))
    )
    (net (code "107") (name "Net-(U1B-PB11)") (class "Default")
      (node (ref "R30") (pin "2") (pintype "passive"))
      (node (ref "U1") (pin "48") (pinfunction "PB11_48") (pintype "passive"))
    )
    (net (code "108") (name "Net-(U1B-PB12)") (class "Default")
      (node (ref "R33") (pin "2") (pintype "passive"))
      (node (ref "U1") (pin "51") (pinfunction "PB12_51") (pintype "passive"))
    )
    (net (code "109") (name "Net-(U1B-PB13)") (class "Default")
      (node (ref "R35") (pin "2") (pintype "passive"))
      (node (ref "U1") (pin "52") (pinfunction "PB13_52") (pintype "passive"))
    )
    (net (code "110") (name "Net-(U1B-PB14)") (class "Default")
      (node (ref "R37") (pin "2") (pintype "passive"))
      (node (ref "U1") (pin "53") (pinfunction "PB14_53") (pintype "passive"))
    )
    (net (code "111") (name "Net-(U1B-PB15)") (class "Default")
      (node (ref "R39") (pin "2") (pintype "passive"))
      (node (ref "U1") (pin "54") (pinfunction "PB15_54") (pintype "passive"))
    )
    (net (code "112") (name "Net-(U1B-nJTRST_{slash}_PB4)") (class "Default")
      (node (ref "R18") (pin "2") (pintype "passive"))
      (node (ref "U1") (pin "90") (pinfunction "nJTRST_/_PB4_90") (pintype "passive"))
    )
    (net (code "113") (name "Net-(U1C-PC10)") (class "Default")
      (node (ref "R41") (pin "2") (pintype "passive"))
      (node (ref "U1") (pin "78") (pinfunction "PC10_78") (pintype "passive"))
    )
    (net (code "114") (name "Net-(U1D-PD6)") (class "Default")
      (node (ref "R20") (pin "2") (pintype "passive"))
      (node (ref "U1") (pin "87") (pinfunction "PD6_87") (pintype "passive"))
    )
    (net (code "115") (name "Net-(U1D-PD7)") (class "Default")
      (node (ref "R23") (pin "2") (pintype "passive"))
      (node (ref "U1") (pin "88") (pinfunction "PD7_88") (pintype "passive"))
    )
    (net (code "116") (name "Net-(U1E-PE0)") (class "Default")
      (node (ref "R11") (pin "2") (pintype "passive"))
      (node (ref "U1") (pin "97") (pinfunction "PE0_97") (pintype "passive"))
    )
    (net (code "117") (name "Net-(U1E-PE1)") (class "Default")
      (node (ref "R13") (pin "2") (pintype "passive"))
      (node (ref "U1") (pin "98") (pinfunction "PE1_98") (pintype "passive"))
    )
    (net (code "118") (name "Net-(U1E-PE5)") (class "Default")
      (node (ref "R21") (pin "2") (pintype "passive"))
      (node (ref "U1") (pin "4") (pinfunction "PE5_4") (pintype "passive"))
    )
    (net (code "119") (name "Net-(U1E-PE7)") (class "Default")
      (node (ref "R25") (pin "2") (pintype "passive"))
      (node (ref "U1") (pin "38") (pinfunction "PE7_38") (pintype "passive"))
    )
    (net (code "120") (name "Net-(U1E-PE8)") (class "Default")
      (node (ref "R27") (pin "2") (pintype "passive"))
      (node (ref "U1") (pin "39") (pinfunction "PE8_39") (pintype "passive"))
    )
    (net (code "121") (name "Net-(U1E-PE9)") (class "Default")
      (node (ref "R29") (pin "2") (pintype "passive"))
      (node (ref "U1") (pin "40") (pinfunction "PE9_40") (pintype "passive"))
    )
    (net (code "122") (name "Net-(U1E-PE11)") (class "Default")
      (node (ref "R31") (pin "2") (pintype "passive"))
      (node (ref "U1") (pin "42") (pinfunction "PE11_42") (pintype "passive"))
    )
    (net (code "123") (name "Net-(U1E-PE12)") (class "Default")
      (node (ref "R34") (pin "2") (pintype "passive"))
      (node (ref "U1") (pin "43") (pinfunction "PE12_43") (pintype "passive"))
    )
    (net (code "124") (name "Net-(U1E-PE14)") (class "Default")
      (node (ref "R38") (pin "2") (pintype "passive"))
      (node (ref "U1") (pin "45") (pinfunction "PE14_45") (pintype "passive"))
    )
    (net (code "125") (name "unconnected-(J1-NC-Pad8)") (class "Default")
      (node (ref "J1") (pin "8") (pinfunction "NC_8") (pintype "passive"))
    )
    (net (code "126") (name "unconnected-(J1-SWO-Pad6)") (class "Default")
      (node (ref "J1") (pin "6") (pinfunction "SWO_6") (pintype "passive"))
    )
    (net (code "127") (name "unconnected-(U1A-PA8-Pad67)") (class "Default")
      (node (ref "U1") (pin "67") (pinfunction "PA8_67") (pintype "passive"))
    )
    (net (code "128") (name "unconnected-(U1C-PC9-Pad66)") (class "Default")
      (node (ref "U1") (pin "66") (pinfunction "PC9_66") (pintype "passive"))
    )
    (net (code "129") (name "unconnected-(U1C-PC11-Pad79)") (class "Default")
      (node (ref "U1") (pin "79") (pinfunction "PC11_79") (pintype "passive"))
    )
    (net (code "130") (name "unconnected-(U1C-PC12-Pad80)") (class "Default")
      (node (ref "U1") (pin "80") (pinfunction "PC12_80") (pintype "passive"))
    )
    (net (code "131") (name "unconnected-(U1C-PC13-Pad7)") (class "Default")
      (node (ref "U1") (pin "7") (pinfunction "PC13_7") (pintype "passive"))
    )
    (net (code "132") (name "unconnected-(U1C-PC14_{slash}_OSC32_IN-Pad8)") (class "Default")
      (node (ref "U1") (pin "8") (pinfunction "PC14_/_OSC32_IN_8") (pintype "passive"))
    )
    (net (code "133") (name "unconnected-(U1C-PC15_{slash}_OSC32_OUT-Pad9)") (class "Default")
      (node (ref "U1") (pin "9") (pinfunction "PC15_/_OSC32_OUT_9") (pintype "passive"))
    )
    (net (code "134") (name "unconnected-(U1D-PD0-Pad81)") (class "Default")
      (node (ref "U1") (pin "81") (pinfunction "PD0_81") (pintype "passive"))
    )
    (net (code "135") (name "unconnected-(U1D-PD1-Pad82)") (class "Default")
      (node (ref "U1") (pin "82") (pinfunction "PD1_82") (pintype "passive"))
    )
    (net (code "136") (name "unconnected-(U1E-PE2-Pad1)") (class "Default")
      (node (ref "U1") (pin "1") (pinfunction "PE2_1") (pintype "passive"))
    )
    (net (code "137") (name "unconnected-(U1E-PE3-Pad2)") (class "Default")
      (node (ref "U1") (pin "2") (pinfunction "PE3_2") (pintype "passive"))
    )
    (net (code "138") (name "unconnected-(U1E-PE4-Pad3)") (class "Default")
      (node (ref "U1") (pin "3") (pinfunction "PE4_3") (pintype "passive"))
    )
    (net (code "139") (name "unconnected-(U1E-PE10-Pad41)") (class "Default")
      (node (ref "U1") (pin "41") (pinfunction "PE10_41") (pintype "passive"))
    )
    (net (code "140") (name "unconnected-(U1E-PE15-Pad46)") (class "Default")
      (node (ref "U1") (pin "46") (pinfunction "PE15_46") (pintype "passive"))
    )
  )
)
